# SENSOR.net
KiCad netlist of a schematic drawn in Altium Designer
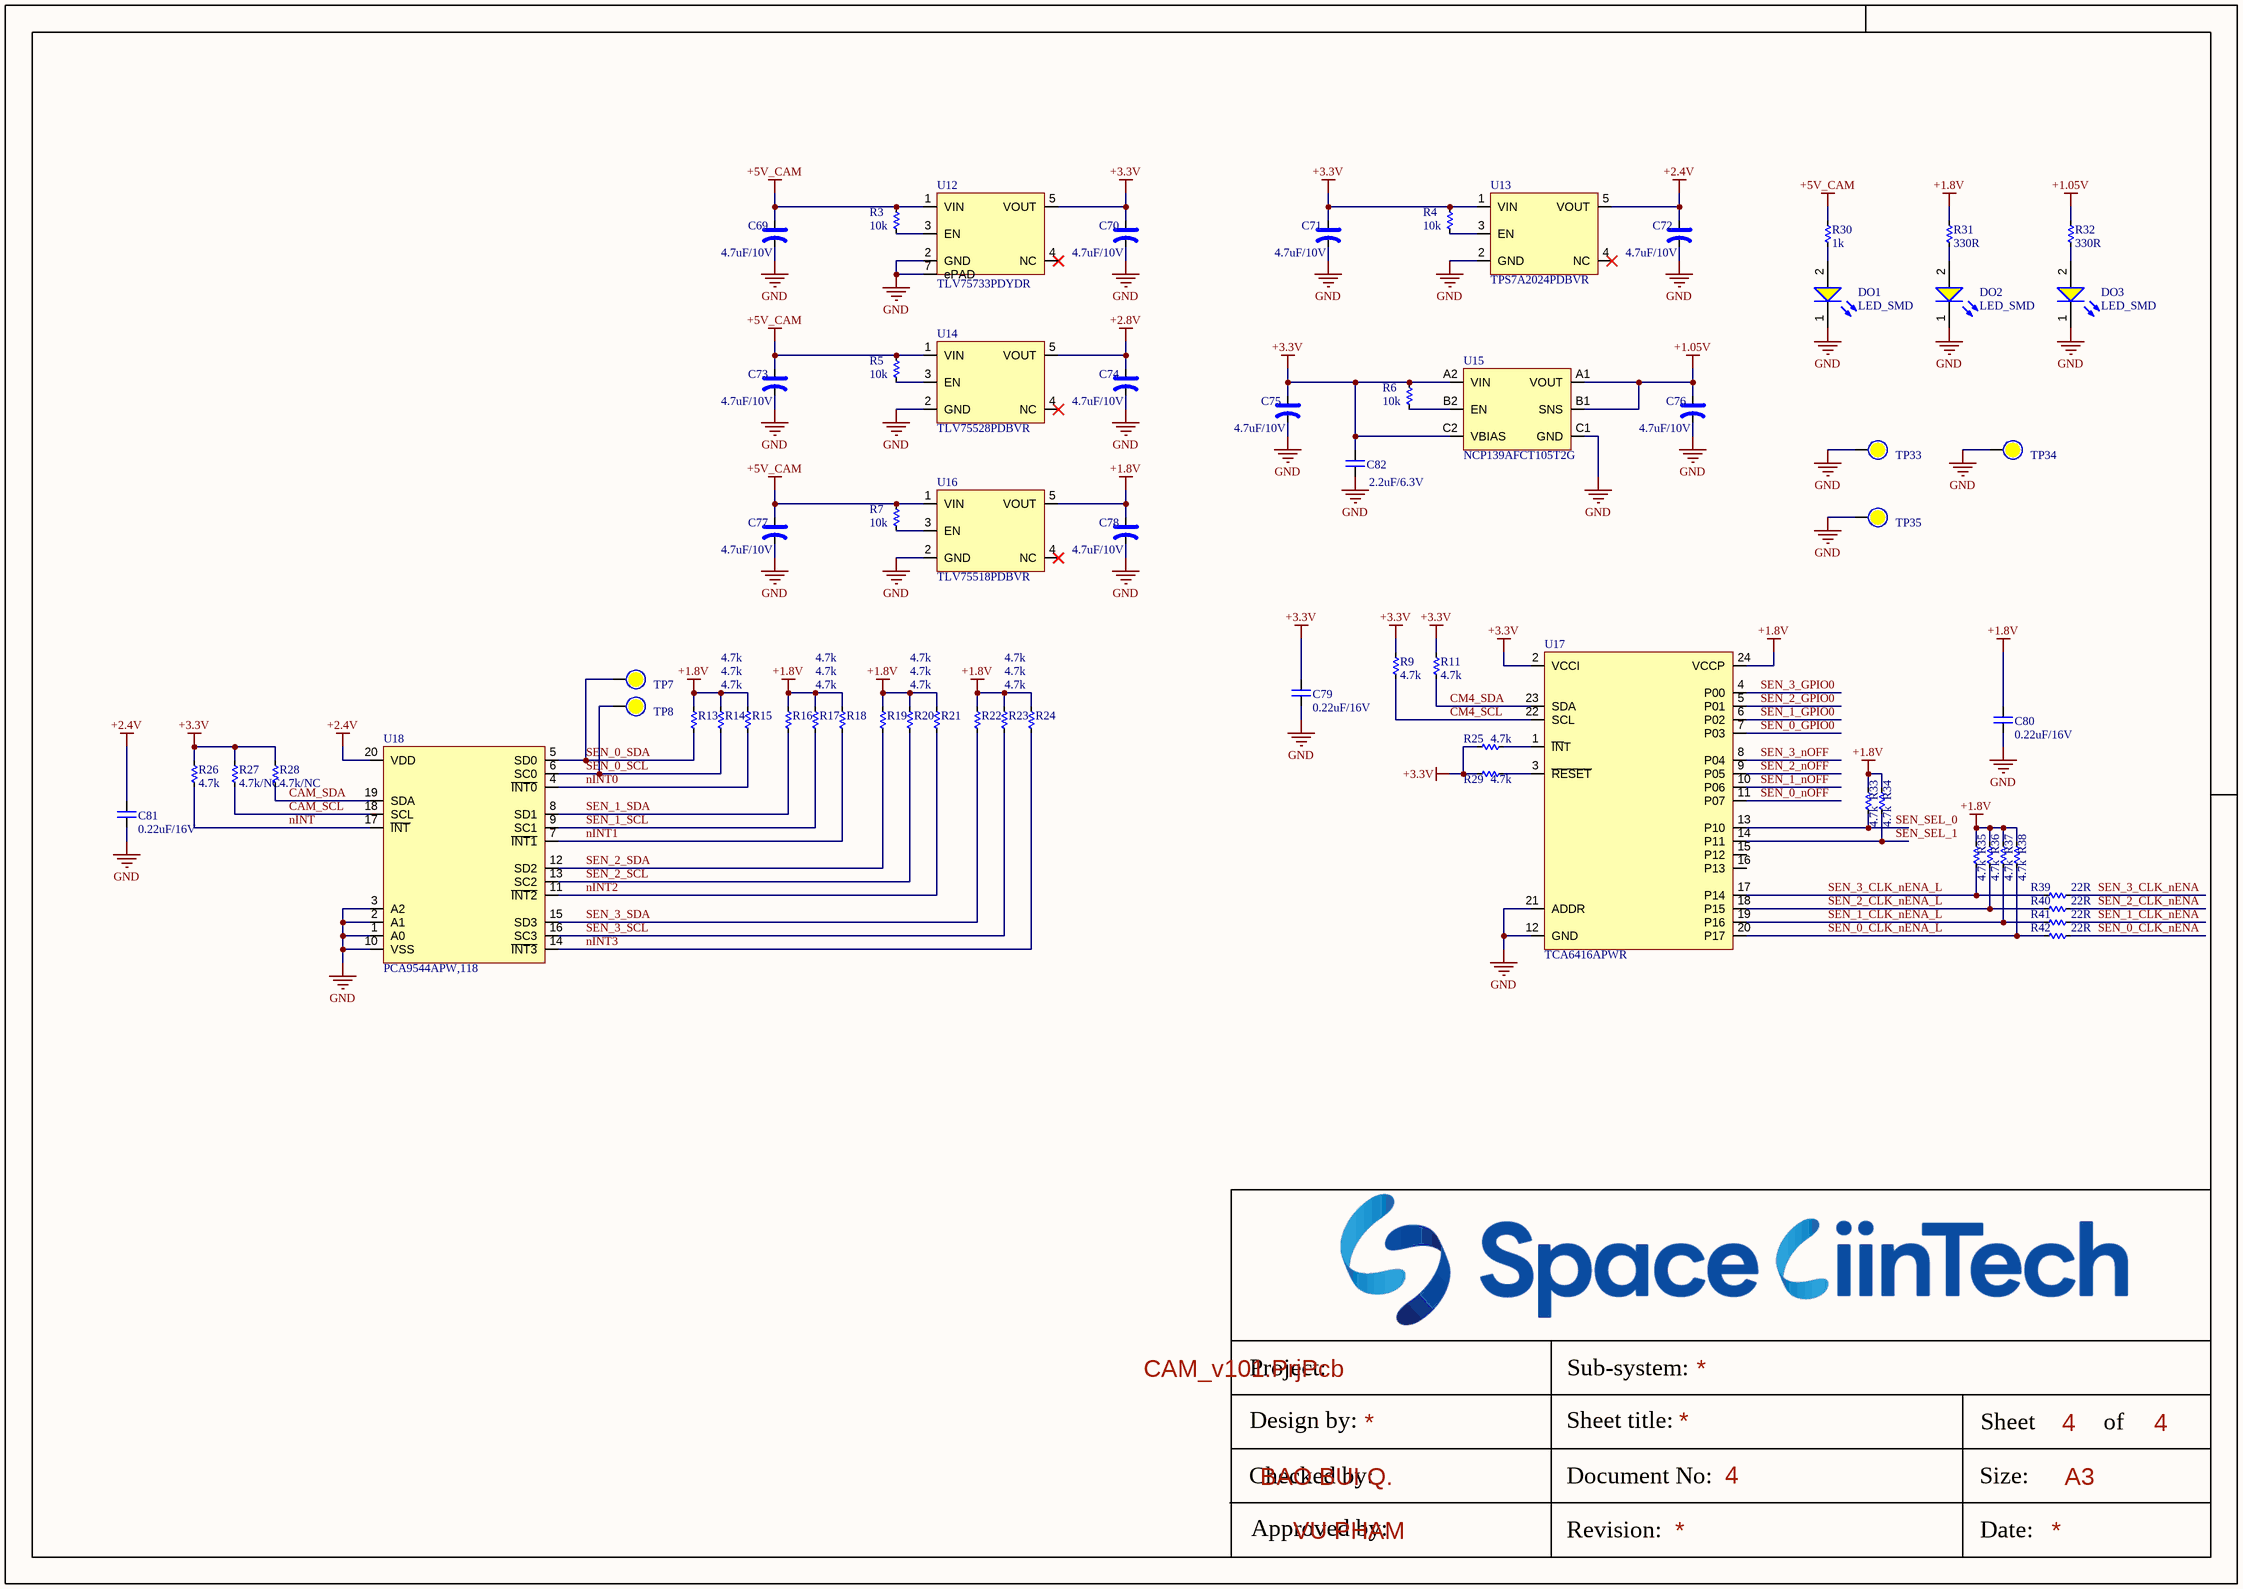
[diagram p0: SENSOR.SchDoc]

(export (version "E")
  (design (tool "Eeschema 10.0.6"))
  (components
    (comp (ref "C69")
      (value "4.7uF/10V")
      (footprint "CAP_MP_1608X90")
      (description "CAP_Polarization")
      (fields (field (name "PUBLISHER") "Altium Limited"))
      (libsource (lib "LABLIB") (part "CAP_TH"))
    )
    (comp (ref "C70")
      (value "4.7uF/10V")
      (footprint "CAP_MP_1608X90")
      (description "CAP_Polarization")
      (fields (field (name "PUBLISHER") "Altium Limited"))
      (libsource (lib "LABLIB") (part "CAP_TH"))
    )
    (comp (ref "C71")
      (value "4.7uF/10V")
      (footprint "CAP_MP_1608X90")
      (description "CAP_Polarization")
      (fields (field (name "PUBLISHER") "Altium Limited"))
      (libsource (lib "LABLIB") (part "CAP_TH"))
    )
    (comp (ref "C72")
      (value "4.7uF/10V")
      (footprint "CAP_MP_1608X90")
      (description "CAP_Polarization")
      (fields (field (name "PUBLISHER") "Altium Limited"))
      (libsource (lib "LABLIB") (part "CAP_TH"))
    )
    (comp (ref "C73")
      (value "4.7uF/10V")
      (footprint "CAP_MP_1608X90")
      (description "CAP_Polarization")
      (fields (field (name "PUBLISHER") "Altium Limited"))
      (libsource (lib "LABLIB") (part "CAP_TH"))
    )
    (comp (ref "C74")
      (value "4.7uF/10V")
      (footprint "CAP_MP_1608X90")
      (description "CAP_Polarization")
      (fields (field (name "PUBLISHER") "Altium Limited"))
      (libsource (lib "LABLIB") (part "CAP_TH"))
    )
    (comp (ref "C75")
      (value "4.7uF/10V")
      (footprint "CAP_MP_1608X90")
      (description "CAP_Polarization")
      (fields (field (name "PUBLISHER") "Altium Limited"))
      (libsource (lib "LABLIB") (part "CAP_TH"))
    )
    (comp (ref "C76")
      (value "4.7uF/10V")
      (footprint "CAP_MP_1608X90")
      (description "CAP_Polarization")
      (fields (field (name "PUBLISHER") "Altium Limited"))
      (libsource (lib "LABLIB") (part "CAP_TH"))
    )
    (comp (ref "C77")
      (value "4.7uF/10V")
      (footprint "CAP_MP_1608X90")
      (description "CAP_Polarization")
      (fields (field (name "PUBLISHER") "Altium Limited"))
      (libsource (lib "LABLIB") (part "CAP_TH"))
    )
    (comp (ref "C78")
      (value "4.7uF/10V")
      (footprint "CAP_MP_1608X90")
      (description "CAP_Polarization")
      (fields (field (name "PUBLISHER") "Altium Limited"))
      (libsource (lib "LABLIB") (part "CAP_TH"))
    )
    (comp (ref "C79")
      (value "0.22uF/16V")
      (footprint "CAP_C_1005X60")
      (description "CAP_Chip")
      (libsource (lib "LABLIB") (part "CAP_SMD"))
    )
    (comp (ref "C80")
      (value "0.22uF/16V")
      (footprint "CAP_C_1005X60")
      (description "CAP_Chip")
      (libsource (lib "LABLIB") (part "CAP_SMD"))
    )
    (comp (ref "C81")
      (value "0.22uF/16V")
      (footprint "CAP_C_1005X60")
      (description "CAP_Chip")
      (libsource (lib "LABLIB") (part "CAP_SMD"))
    )
    (comp (ref "C82")
      (value "2.2uF/6.3V")
      (footprint "CAP_C_1005X60")
      (description "CAP_Chip")
      (libsource (lib "LABLIB") (part "CAP_SMD"))
    )
    (comp (ref "DO1") (value "LED_SMD") (footprint "LED_0603") (libsource (lib "LABLIB") (part "LED_SMD")))
    (comp (ref "DO2") (value "LED_SMD") (footprint "LED_0603") (libsource (lib "LABLIB") (part "LED_SMD")))
    (comp (ref "DO3") (value "LED_SMD") (footprint "LED_0603") (libsource (lib "LABLIB") (part "LED_SMD")))
    (comp (ref "R3")
      (value "10k")
      (footprint "RES_C_1005X40")
      (description "RES-Chip")
      (fields
        (field (name "MANUFACTURER") "Generic Components")
        (field (name "PUBLISHER") "Altium Hobart Technology Centre")
      )
      (libsource (lib "LABLIB") (part "RES-SMD"))
    )
    (comp (ref "R4")
      (value "10k")
      (footprint "RES_C_1005X40")
      (description "RES-Chip")
      (fields
        (field (name "MANUFACTURER") "Generic Components")
        (field (name "PUBLISHER") "Altium Hobart Technology Centre")
      )
      (libsource (lib "LABLIB") (part "RES-SMD"))
    )
    (comp (ref "R5")
      (value "10k")
      (footprint "RES_C_1005X40")
      (description "RES-Chip")
      (fields
        (field (name "MANUFACTURER") "Generic Components")
        (field (name "PUBLISHER") "Altium Hobart Technology Centre")
      )
      (libsource (lib "LABLIB") (part "RES-SMD"))
    )
    (comp (ref "R6")
      (value "10k")
      (footprint "RES_C_1005X40")
      (description "RES-Chip")
      (fields
        (field (name "MANUFACTURER") "Generic Components")
        (field (name "PUBLISHER") "Altium Hobart Technology Centre")
      )
      (libsource (lib "LABLIB") (part "RES-SMD"))
    )
    (comp (ref "R7")
      (value "10k")
      (footprint "RES_C_1005X40")
      (description "RES-Chip")
      (fields
        (field (name "MANUFACTURER") "Generic Components")
        (field (name "PUBLISHER") "Altium Hobart Technology Centre")
      )
      (libsource (lib "LABLIB") (part "RES-SMD"))
    )
    (comp (ref "R9")
      (value "4.7k")
      (footprint "RES_C_1005X40")
      (description "RES-Chip")
      (fields
        (field (name "MANUFACTURER") "Generic Components")
        (field (name "PUBLISHER") "Altium Hobart Technology Centre")
      )
      (libsource (lib "LABLIB") (part "RES-SMD"))
    )
    (comp (ref "R11")
      (value "4.7k")
      (footprint "RES_C_1005X40")
      (description "RES-Chip")
      (fields
        (field (name "MANUFACTURER") "Generic Components")
        (field (name "PUBLISHER") "Altium Hobart Technology Centre")
      )
      (libsource (lib "LABLIB") (part "RES-SMD"))
    )
    (comp (ref "R13")
      (value "4.7k")
      (footprint "RES_C_1005X40")
      (description "RES-Chip")
      (fields
        (field (name "MANUFACTURER") "Generic Components")
        (field (name "PUBLISHER") "Altium Hobart Technology Centre")
      )
      (libsource (lib "LABLIB") (part "RES-SMD"))
    )
    (comp (ref "R14")
      (value "4.7k")
      (footprint "RES_C_1005X40")
      (description "RES-Chip")
      (fields
        (field (name "MANUFACTURER") "Generic Components")
        (field (name "PUBLISHER") "Altium Hobart Technology Centre")
      )
      (libsource (lib "LABLIB") (part "RES-SMD"))
    )
    (comp (ref "R15")
      (value "4.7k")
      (footprint "RES_C_1005X40")
      (description "RES-Chip")
      (fields
        (field (name "MANUFACTURER") "Generic Components")
        (field (name "PUBLISHER") "Altium Hobart Technology Centre")
      )
      (libsource (lib "LABLIB") (part "RES-SMD"))
    )
    (comp (ref "R16")
      (value "4.7k")
      (footprint "RES_C_1005X40")
      (description "RES-Chip")
      (fields
        (field (name "MANUFACTURER") "Generic Components")
        (field (name "PUBLISHER") "Altium Hobart Technology Centre")
      )
      (libsource (lib "LABLIB") (part "RES-SMD"))
    )
    (comp (ref "R17")
      (value "4.7k")
      (footprint "RES_C_1005X40")
      (description "RES-Chip")
      (fields
        (field (name "MANUFACTURER") "Generic Components")
        (field (name "PUBLISHER") "Altium Hobart Technology Centre")
      )
      (libsource (lib "LABLIB") (part "RES-SMD"))
    )
    (comp (ref "R18")
      (value "4.7k")
      (footprint "RES_C_1005X40")
      (description "RES-Chip")
      (fields
        (field (name "MANUFACTURER") "Generic Components")
        (field (name "PUBLISHER") "Altium Hobart Technology Centre")
      )
      (libsource (lib "LABLIB") (part "RES-SMD"))
    )
    (comp (ref "R19")
      (value "4.7k")
      (footprint "RES_C_1005X40")
      (description "RES-Chip")
      (fields
        (field (name "MANUFACTURER") "Generic Components")
        (field (name "PUBLISHER") "Altium Hobart Technology Centre")
      )
      (libsource (lib "LABLIB") (part "RES-SMD"))
    )
    (comp (ref "R20")
      (value "4.7k")
      (footprint "RES_C_1005X40")
      (description "RES-Chip")
      (fields
        (field (name "MANUFACTURER") "Generic Components")
        (field (name "PUBLISHER") "Altium Hobart Technology Centre")
      )
      (libsource (lib "LABLIB") (part "RES-SMD"))
    )
    (comp (ref "R21")
      (value "4.7k")
      (footprint "RES_C_1005X40")
      (description "RES-Chip")
      (fields
        (field (name "MANUFACTURER") "Generic Components")
        (field (name "PUBLISHER") "Altium Hobart Technology Centre")
      )
      (libsource (lib "LABLIB") (part "RES-SMD"))
    )
    (comp (ref "R22")
      (value "4.7k")
      (footprint "RES_C_1005X40")
      (description "RES-Chip")
      (fields
        (field (name "MANUFACTURER") "Generic Components")
        (field (name "PUBLISHER") "Altium Hobart Technology Centre")
      )
      (libsource (lib "LABLIB") (part "RES-SMD"))
    )
    (comp (ref "R23")
      (value "4.7k")
      (footprint "RES_C_1005X40")
      (description "RES-Chip")
      (fields
        (field (name "MANUFACTURER") "Generic Components")
        (field (name "PUBLISHER") "Altium Hobart Technology Centre")
      )
      (libsource (lib "LABLIB") (part "RES-SMD"))
    )
    (comp (ref "R24")
      (value "4.7k")
      (footprint "RES_C_1005X40")
      (description "RES-Chip")
      (fields
        (field (name "MANUFACTURER") "Generic Components")
        (field (name "PUBLISHER") "Altium Hobart Technology Centre")
      )
      (libsource (lib "LABLIB") (part "RES-SMD"))
    )
    (comp (ref "R25")
      (value "4.7k")
      (footprint "RES_C_1005X40")
      (description "RES-Chip")
      (fields
        (field (name "MANUFACTURER") "Generic Components")
        (field (name "PUBLISHER") "Altium Hobart Technology Centre")
      )
      (libsource (lib "LABLIB") (part "RES-SMD"))
    )
    (comp (ref "R26")
      (value "4.7k")
      (footprint "RES_C_1005X40")
      (description "RES-Chip")
      (fields
        (field (name "MANUFACTURER") "Generic Components")
        (field (name "PUBLISHER") "Altium Hobart Technology Centre")
      )
      (libsource (lib "LABLIB") (part "RES-SMD"))
    )
    (comp (ref "R27")
      (value "4.7k/NC")
      (footprint "RES_C_1005X40")
      (description "RES-Chip")
      (fields
        (field (name "MANUFACTURER") "Generic Components")
        (field (name "PUBLISHER") "Altium Hobart Technology Centre")
      )
      (libsource (lib "LABLIB") (part "RES-SMD"))
    )
    (comp (ref "R28")
      (value "4.7k/NC")
      (footprint "RES_C_1005X40")
      (description "RES-Chip")
      (fields
        (field (name "MANUFACTURER") "Generic Components")
        (field (name "PUBLISHER") "Altium Hobart Technology Centre")
      )
      (libsource (lib "LABLIB") (part "RES-SMD"))
    )
    (comp (ref "R29")
      (value "4.7k")
      (footprint "RES_C_1005X40")
      (description "RES-Chip")
      (fields
        (field (name "MANUFACTURER") "Generic Components")
        (field (name "PUBLISHER") "Altium Hobart Technology Centre")
      )
      (libsource (lib "LABLIB") (part "RES-SMD"))
    )
    (comp (ref "R30")
      (value "1k")
      (footprint "RES_C_1005X40")
      (description "RES-Chip")
      (fields
        (field (name "MANUFACTURER") "Generic Components")
        (field (name "PUBLISHER") "Altium Hobart Technology Centre")
      )
      (libsource (lib "LABLIB") (part "RES-SMD"))
    )
    (comp (ref "R31")
      (value "330R")
      (footprint "RES_C_1005X40")
      (description "RES-Chip")
      (fields
        (field (name "MANUFACTURER") "Generic Components")
        (field (name "PUBLISHER") "Altium Hobart Technology Centre")
      )
      (libsource (lib "LABLIB") (part "RES-SMD"))
    )
    (comp (ref "R32")
      (value "330R")
      (footprint "RES_C_1005X40")
      (description "RES-Chip")
      (fields
        (field (name "MANUFACTURER") "Generic Components")
        (field (name "PUBLISHER") "Altium Hobart Technology Centre")
      )
      (libsource (lib "LABLIB") (part "RES-SMD"))
    )
    (comp (ref "R33")
      (value "4.7k")
      (footprint "RES_C_1005X40")
      (description "RES-Chip")
      (fields
        (field (name "MANUFACTURER") "Generic Components")
        (field (name "PUBLISHER") "Altium Hobart Technology Centre")
      )
      (libsource (lib "LABLIB") (part "RES-SMD"))
    )
    (comp (ref "R34")
      (value "4.7k")
      (footprint "RES_C_1005X40")
      (description "RES-Chip")
      (fields
        (field (name "MANUFACTURER") "Generic Components")
        (field (name "PUBLISHER") "Altium Hobart Technology Centre")
      )
      (libsource (lib "LABLIB") (part "RES-SMD"))
    )
    (comp (ref "R35")
      (value "4.7k")
      (footprint "RES_C_1005X40")
      (description "RES-Chip")
      (fields
        (field (name "MANUFACTURER") "Generic Components")
        (field (name "PUBLISHER") "Altium Hobart Technology Centre")
      )
      (libsource (lib "LABLIB") (part "RES-SMD"))
    )
    (comp (ref "R36")
      (value "4.7k")
      (footprint "RES_C_1005X40")
      (description "RES-Chip")
      (fields
        (field (name "MANUFACTURER") "Generic Components")
        (field (name "PUBLISHER") "Altium Hobart Technology Centre")
      )
      (libsource (lib "LABLIB") (part "RES-SMD"))
    )
    (comp (ref "R37")
      (value "4.7k")
      (footprint "RES_C_1005X40")
      (description "RES-Chip")
      (fields
        (field (name "MANUFACTURER") "Generic Components")
        (field (name "PUBLISHER") "Altium Hobart Technology Centre")
      )
      (libsource (lib "LABLIB") (part "RES-SMD"))
    )
    (comp (ref "R38")
      (value "4.7k")
      (footprint "RES_C_1005X40")
      (description "RES-Chip")
      (fields
        (field (name "MANUFACTURER") "Generic Components")
        (field (name "PUBLISHER") "Altium Hobart Technology Centre")
      )
      (libsource (lib "LABLIB") (part "RES-SMD"))
    )
    (comp (ref "R39")
      (value "22R")
      (footprint "RES_C_1005X40")
      (description "RES-Chip")
      (fields
        (field (name "MANUFACTURER") "Generic Components")
        (field (name "PUBLISHER") "Altium Hobart Technology Centre")
      )
      (libsource (lib "LABLIB") (part "RES-SMD"))
    )
    (comp (ref "R40")
      (value "22R")
      (footprint "RES_C_1005X40")
      (description "RES-Chip")
      (fields
        (field (name "MANUFACTURER") "Generic Components")
        (field (name "PUBLISHER") "Altium Hobart Technology Centre")
      )
      (libsource (lib "LABLIB") (part "RES-SMD"))
    )
    (comp (ref "R41")
      (value "22R")
      (footprint "RES_C_1005X40")
      (description "RES-Chip")
      (fields
        (field (name "MANUFACTURER") "Generic Components")
        (field (name "PUBLISHER") "Altium Hobart Technology Centre")
      )
      (libsource (lib "LABLIB") (part "RES-SMD"))
    )
    (comp (ref "R42")
      (value "22R")
      (footprint "RES_C_1005X40")
      (description "RES-Chip")
      (fields
        (field (name "MANUFACTURER") "Generic Components")
        (field (name "PUBLISHER") "Altium Hobart Technology Centre")
      )
      (libsource (lib "LABLIB") (part "RES-SMD"))
    )
    (comp (ref "TP7")
      (value "~")
      (footprint "Testpoint_80")
      (description "Test Point")
      (libsource (lib "LABLIB") (part "Test Point"))
    )
    (comp (ref "TP8")
      (value "~")
      (footprint "Testpoint_80")
      (description "Test Point")
      (libsource (lib "LABLIB") (part "Test Point"))
    )
    (comp (ref "TP33")
      (value "~")
      (footprint "Testpoint_80")
      (description "Test Point")
      (libsource (lib "LABLIB") (part "Test Point"))
    )
    (comp (ref "TP34")
      (value "~")
      (footprint "Testpoint_80")
      (description "Test Point")
      (libsource (lib "LABLIB") (part "Test Point"))
    )
    (comp (ref "TP35")
      (value "~")
      (footprint "Testpoint_80")
      (description "Test Point")
      (libsource (lib "LABLIB") (part "Test Point"))
    )
    (comp (ref "U12")
      (value "TLV75733PDYDR")
      (footprint "SOT25-EPAD")
      (libsource (lib "CAMERA_SchLib") (part "IC_POWER_TLV75733PDYDR"))
    )
    (comp (ref "U13")
      (value "TPS7A2024PDBVR")
      (footprint "SOT25")
      (libsource (lib "CAMERA_SchLib") (part "IC_POWER_AP7347DQ"))
    )
    (comp (ref "U14")
      (value "TLV75528PDBVR")
      (footprint "SOT25")
      (libsource (lib "CAMERA_SchLib") (part "IC_POWER_AP7347DQ"))
    )
    (comp (ref "U15")
      (value "NCP139AFCT105T2G")
      (footprint "WLCSP6")
      (libsource (lib "CAMERA_SchLib") (part "IC_POWER_NCP139AFCT105T2G"))
    )
    (comp (ref "U16")
      (value "TLV75518PDBVR")
      (footprint "SOT25")
      (libsource (lib "CAMERA_SchLib") (part "IC_POWER_AP7347DQ"))
    )
    (comp (ref "U17")
      (value "TCA6416APWR")
      (footprint "SOP65P440W-24N")
      (libsource (lib "CAMERA_SchLib") (part "IC_I2Cto16IO_TCA6416APWR"))
    )
    (comp (ref "U18")
      (value "PCA9544APW,118")
      (footprint "SOP65P440W_20")
      (libsource (lib "CAMERA_SchLib") (part "IC_I2CSW1to4_PCA9544APW,118"))
    )
  )
  (nets
    (net (code "1") (name "+1.05V") (class "Default")
      (node (ref "C76") (pin "1") (pinfunction "1_1") (pintype "passive"))
      (node (ref "R32") (pin "1") (pinfunction "1_1") (pintype "passive"))
      (node (ref "U15") (pin "A1") (pinfunction "VOUT_A1") (pintype "passive"))
      (node (ref "U15") (pin "B1") (pinfunction "SNS_B1") (pintype "passive"))
    )
    (net (code "2") (name "+1.8V") (class "Default")
      (node (ref "C78") (pin "1") (pinfunction "1_1") (pintype "passive"))
      (node (ref "C80") (pin "2") (pinfunction "2_2") (pintype "passive"))
      (node (ref "R13") (pin "1") (pinfunction "1_1") (pintype "passive"))
      (node (ref "R14") (pin "1") (pinfunction "1_1") (pintype "passive"))
      (node (ref "R15") (pin "1") (pinfunction "1_1") (pintype "passive"))
      (node (ref "R16") (pin "1") (pinfunction "1_1") (pintype "passive"))
      (node (ref "R17") (pin "1") (pinfunction "1_1") (pintype "passive"))
      (node (ref "R18") (pin "1") (pinfunction "1_1") (pintype "passive"))
      (node (ref "R19") (pin "1") (pinfunction "1_1") (pintype "passive"))
      (node (ref "R20") (pin "1") (pinfunction "1_1") (pintype "passive"))
      (node (ref "R21") (pin "1") (pinfunction "1_1") (pintype "passive"))
      (node (ref "R22") (pin "1") (pinfunction "1_1") (pintype "passive"))
      (node (ref "R23") (pin "1") (pinfunction "1_1") (pintype "passive"))
      (node (ref "R24") (pin "1") (pinfunction "1_1") (pintype "passive"))
      (node (ref "R31") (pin "1") (pinfunction "1_1") (pintype "passive"))
      (node (ref "R33") (pin "1") (pinfunction "1_1") (pintype "passive"))
      (node (ref "R34") (pin "1") (pinfunction "1_1") (pintype "passive"))
      (node (ref "R35") (pin "1") (pinfunction "1_1") (pintype "passive"))
      (node (ref "R36") (pin "1") (pinfunction "1_1") (pintype "passive"))
      (node (ref "R37") (pin "1") (pinfunction "1_1") (pintype "passive"))
      (node (ref "R38") (pin "1") (pinfunction "1_1") (pintype "passive"))
      (node (ref "U16") (pin "5") (pinfunction "VOUT_5") (pintype "passive"))
      (node (ref "U17") (pin "24") (pinfunction "VCCP_24") (pintype "passive"))
    )
    (net (code "3") (name "+2.4V") (class "Default")
      (node (ref "C72") (pin "1") (pinfunction "1_1") (pintype "passive"))
      (node (ref "C81") (pin "2") (pinfunction "2_2") (pintype "passive"))
      (node (ref "U13") (pin "5") (pinfunction "VOUT_5") (pintype "passive"))
      (node (ref "U18") (pin "20") (pinfunction "VDD_20") (pintype "passive"))
    )
    (net (code "4") (name "+2.8V") (class "Default")
      (node (ref "C74") (pin "1") (pinfunction "1_1") (pintype "passive"))
      (node (ref "U14") (pin "5") (pinfunction "VOUT_5") (pintype "passive"))
    )
    (net (code "5") (name "+3.3V") (class "Default")
      (node (ref "C70") (pin "1") (pinfunction "1_1") (pintype "passive"))
      (node (ref "C71") (pin "1") (pinfunction "1_1") (pintype "passive"))
      (node (ref "C75") (pin "1") (pinfunction "1_1") (pintype "passive"))
      (node (ref "C79") (pin "2") (pinfunction "2_2") (pintype "passive"))
      (node (ref "C82") (pin "2") (pinfunction "2_2") (pintype "passive"))
      (node (ref "R11") (pin "1") (pinfunction "1_1") (pintype "passive"))
      (node (ref "R25") (pin "1") (pinfunction "1_1") (pintype "passive"))
      (node (ref "R26") (pin "1") (pinfunction "1_1") (pintype "passive"))
      (node (ref "R27") (pin "1") (pinfunction "1_1") (pintype "passive"))
      (node (ref "R28") (pin "1") (pinfunction "1_1") (pintype "passive"))
      (node (ref "R29") (pin "1") (pinfunction "1_1") (pintype "passive"))
      (node (ref "R4") (pin "2") (pinfunction "2_2") (pintype "passive"))
      (node (ref "R6") (pin "2") (pinfunction "2_2") (pintype "passive"))
      (node (ref "R9") (pin "1") (pinfunction "1_1") (pintype "passive"))
      (node (ref "U12") (pin "5") (pinfunction "VOUT_5") (pintype "passive"))
      (node (ref "U13") (pin "1") (pinfunction "VIN_1") (pintype "passive"))
      (node (ref "U15") (pin "A2") (pinfunction "VIN_A2") (pintype "passive"))
      (node (ref "U15") (pin "C2") (pinfunction "VBIAS_C2") (pintype "passive"))
      (node (ref "U17") (pin "2") (pinfunction "VCCI_2") (pintype "passive"))
    )
    (net (code "6") (name "+5V_CAM") (class "Default")
      (node (ref "C69") (pin "1") (pinfunction "1_1") (pintype "passive"))
      (node (ref "C73") (pin "1") (pinfunction "1_1") (pintype "passive"))
      (node (ref "C77") (pin "1") (pinfunction "1_1") (pintype "passive"))
      (node (ref "R3") (pin "2") (pinfunction "2_2") (pintype "passive"))
      (node (ref "R30") (pin "1") (pinfunction "1_1") (pintype "passive"))
      (node (ref "R5") (pin "2") (pinfunction "2_2") (pintype "passive"))
      (node (ref "R7") (pin "2") (pinfunction "2_2") (pintype "passive"))
      (node (ref "U12") (pin "1") (pinfunction "VIN_1") (pintype "passive"))
      (node (ref "U14") (pin "1") (pinfunction "VIN_1") (pintype "passive"))
      (node (ref "U16") (pin "1") (pinfunction "VIN_1") (pintype "passive"))
    )
    (net (code "7") (name "/CAM_SCL") (class "Default")
      (node (ref "R27") (pin "2") (pinfunction "2_2") (pintype "passive"))
      (node (ref "U18") (pin "18") (pinfunction "SCL_18") (pintype "passive"))
    )
    (net (code "8") (name "/CAM_SDA") (class "Default")
      (node (ref "R28") (pin "2") (pinfunction "2_2") (pintype "passive"))
      (node (ref "U18") (pin "19") (pinfunction "SDA_19") (pintype "passive"))
    )
    (net (code "9") (name "/CM4_SCL") (class "Default")
      (node (ref "R9") (pin "2") (pinfunction "2_2") (pintype "passive"))
      (node (ref "U17") (pin "22") (pinfunction "SCL_22") (pintype "passive"))
    )
    (net (code "10") (name "/CM4_SDA") (class "Default")
      (node (ref "R11") (pin "2") (pinfunction "2_2") (pintype "passive"))
      (node (ref "U17") (pin "23") (pinfunction "SDA_23") (pintype "passive"))
    )
    (net (code "11") (name "/SEN_0_CLK_nENA") (class "Default")
      (node (ref "R42") (pin "1") (pinfunction "1_1") (pintype "passive"))
    )
    (net (code "12") (name "/SEN_0_CLK_nENA_L") (class "Default")
      (node (ref "R38") (pin "2") (pinfunction "2_2") (pintype "passive"))
      (node (ref "R42") (pin "2") (pinfunction "2_2") (pintype "passive"))
      (node (ref "U17") (pin "20") (pinfunction "P17_20") (pintype "passive"))
    )
    (net (code "13") (name "/SEN_0_GPIO0") (class "Default")
      (node (ref "U17") (pin "7") (pinfunction "P03_7") (pintype "passive"))
    )
    (net (code "14") (name "/SEN_0_SCL") (class "Default")
      (node (ref "R14") (pin "2") (pinfunction "2_2") (pintype "passive"))
      (node (ref "TP8") (pin "0") (pinfunction "0_0") (pintype "passive"))
      (node (ref "U18") (pin "6") (pinfunction "SC0_6") (pintype "passive"))
    )
    (net (code "15") (name "/SEN_0_SDA") (class "Default")
      (node (ref "R13") (pin "2") (pinfunction "2_2") (pintype "passive"))
      (node (ref "TP7") (pin "0") (pinfunction "0_0") (pintype "passive"))
      (node (ref "U18") (pin "5") (pinfunction "SD0_5") (pintype "passive"))
    )
    (net (code "16") (name "/SEN_0_nOFF") (class "Default")
      (node (ref "U17") (pin "11") (pinfunction "P07_11") (pintype "passive"))
    )
    (net (code "17") (name "/SEN_1_CLK_nENA") (class "Default")
      (node (ref "R41") (pin "1") (pinfunction "1_1") (pintype "passive"))
    )
    (net (code "18") (name "/SEN_1_CLK_nENA_L") (class "Default")
      (node (ref "R37") (pin "2") (pinfunction "2_2") (pintype "passive"))
      (node (ref "R41") (pin "2") (pinfunction "2_2") (pintype "passive"))
      (node (ref "U17") (pin "19") (pinfunction "P16_19") (pintype "passive"))
    )
    (net (code "19") (name "/SEN_1_GPIO0") (class "Default")
      (node (ref "U17") (pin "6") (pinfunction "P02_6") (pintype "passive"))
    )
    (net (code "20") (name "/SEN_1_SCL") (class "Default")
      (node (ref "R17") (pin "2") (pinfunction "2_2") (pintype "passive"))
      (node (ref "U18") (pin "9") (pinfunction "SC1_9") (pintype "passive"))
    )
    (net (code "21") (name "/SEN_1_SDA") (class "Default")
      (node (ref "R16") (pin "2") (pinfunction "2_2") (pintype "passive"))
      (node (ref "U18") (pin "8") (pinfunction "SD1_8") (pintype "passive"))
    )
    (net (code "22") (name "/SEN_1_nOFF") (class "Default")
      (node (ref "U17") (pin "10") (pinfunction "P06_10") (pintype "passive"))
    )
    (net (code "23") (name "/SEN_2_CLK_nENA") (class "Default")
      (node (ref "R40") (pin "1") (pinfunction "1_1") (pintype "passive"))
    )
    (net (code "24") (name "/SEN_2_CLK_nENA_L") (class "Default")
      (node (ref "R36") (pin "2") (pinfunction "2_2") (pintype "passive"))
      (node (ref "R40") (pin "2") (pinfunction "2_2") (pintype "passive"))
      (node (ref "U17") (pin "18") (pinfunction "P15_18") (pintype "passive"))
    )
    (net (code "25") (name "/SEN_2_GPIO0") (class "Default")
      (node (ref "U17") (pin "5") (pinfunction "P01_5") (pintype "passive"))
    )
    (net (code "26") (name "/SEN_2_SCL") (class "Default")
      (node (ref "R20") (pin "2") (pinfunction "2_2") (pintype "passive"))
      (node (ref "U18") (pin "13") (pinfunction "SC2_13") (pintype "passive"))
    )
    (net (code "27") (name "/SEN_2_SDA") (class "Default")
      (node (ref "R19") (pin "2") (pinfunction "2_2") (pintype "passive"))
      (node (ref "U18") (pin "12") (pinfunction "SD2_12") (pintype "passive"))
    )
    (net (code "28") (name "/SEN_2_nOFF") (class "Default")
      (node (ref "U17") (pin "9") (pinfunction "P05_9") (pintype "passive"))
    )
    (net (code "29") (name "/SEN_3_CLK_nENA") (class "Default")
      (node (ref "R39") (pin "1") (pinfunction "1_1") (pintype "passive"))
    )
    (net (code "30") (name "/SEN_3_CLK_nENA_L") (class "Default")
      (node (ref "R35") (pin "2") (pinfunction "2_2") (pintype "passive"))
      (node (ref "R39") (pin "2") (pinfunction "2_2") (pintype "passive"))
      (node (ref "U17") (pin "17") (pinfunction "P14_17") (pintype "passive"))
    )
    (net (code "31") (name "/SEN_3_GPIO0") (class "Default")
      (node (ref "U17") (pin "4") (pinfunction "P00_4") (pintype "passive"))
    )
    (net (code "32") (name "/SEN_3_SCL") (class "Default")
      (node (ref "R23") (pin "2") (pinfunction "2_2") (pintype "passive"))
      (node (ref "U18") (pin "16") (pinfunction "SC3_16") (pintype "passive"))
    )
    (net (code "33") (name "/SEN_3_SDA") (class "Default")
      (node (ref "R22") (pin "2") (pinfunction "2_2") (pintype "passive"))
      (node (ref "U18") (pin "15") (pinfunction "SD3_15") (pintype "passive"))
    )
    (net (code "34") (name "/SEN_3_nOFF") (class "Default")
      (node (ref "U17") (pin "8") (pinfunction "P04_8") (pintype "passive"))
    )
    (net (code "35") (name "/SEN_SEL_0") (class "Default")
      (node (ref "R33") (pin "2") (pinfunction "2_2") (pintype "passive"))
      (node (ref "U17") (pin "13") (pinfunction "P10_13") (pintype "passive"))
    )
    (net (code "36") (name "/SEN_SEL_1") (class "Default")
      (node (ref "R34") (pin "2") (pinfunction "2_2") (pintype "passive"))
      (node (ref "U17") (pin "14") (pinfunction "P11_14") (pintype "passive"))
    )
    (net (code "37") (name "/nINT") (class "Default")
      (node (ref "R26") (pin "2") (pinfunction "2_2") (pintype "passive"))
      (node (ref "U18") (pin "17") (pinfunction "~{INT}_17") (pintype "passive"))
    )
    (net (code "38") (name "/nINT0") (class "Default")
      (node (ref "R15") (pin "2") (pinfunction "2_2") (pintype "passive"))
      (node (ref "U18") (pin "4") (pinfunction "~{INT0}_4") (pintype "passive"))
    )
    (net (code "39") (name "/nINT1") (class "Default")
      (node (ref "R18") (pin "2") (pinfunction "2_2") (pintype "passive"))
      (node (ref "U18") (pin "7") (pinfunction "~{INT1}_7") (pintype "passive"))
    )
    (net (code "40") (name "/nINT2") (class "Default")
      (node (ref "R21") (pin "2") (pinfunction "2_2") (pintype "passive"))
      (node (ref "U18") (pin "11") (pinfunction "~{INT2}_11") (pintype "passive"))
    )
    (net (code "41") (name "/nINT3") (class "Default")
      (node (ref "R24") (pin "2") (pinfunction "2_2") (pintype "passive"))
      (node (ref "U18") (pin "14") (pinfunction "~{INT3}_14") (pintype "passive"))
    )
    (net (code "42") (name "GND") (class "Default")
      (node (ref "C69") (pin "2") (pinfunction "2_2") (pintype "passive"))
      (node (ref "C70") (pin "2") (pinfunction "2_2") (pintype "passive"))
      (node (ref "C71") (pin "2") (pinfunction "2_2") (pintype "passive"))
      (node (ref "C72") (pin "2") (pinfunction "2_2") (pintype "passive"))
      (node (ref "C73") (pin "2") (pinfunction "2_2") (pintype "passive"))
      (node (ref "C74") (pin "2") (pinfunction "2_2") (pintype "passive"))
      (node (ref "C75") (pin "2") (pinfunction "2_2") (pintype "passive"))
      (node (ref "C76") (pin "2") (pinfunction "2_2") (pintype "passive"))
      (node (ref "C77") (pin "2") (pinfunction "2_2") (pintype "passive"))
      (node (ref "C78") (pin "2") (pinfunction "2_2") (pintype "passive"))
      (node (ref "C79") (pin "1") (pinfunction "1_1") (pintype "passive"))
      (node (ref "C80") (pin "1") (pinfunction "1_1") (pintype "passive"))
      (node (ref "C81") (pin "1") (pinfunction "1_1") (pintype "passive"))
      (node (ref "C82") (pin "1") (pinfunction "1_1") (pintype "passive"))
      (node (ref "DO1") (pin "1") (pinfunction "K_1") (pintype "passive"))
      (node (ref "DO2") (pin "1") (pinfunction "K_1") (pintype "passive"))
      (node (ref "DO3") (pin "1") (pinfunction "K_1") (pintype "passive"))
      (node (ref "TP33") (pin "0") (pinfunction "0_0") (pintype "passive"))
      (node (ref "TP34") (pin "0") (pinfunction "0_0") (pintype "passive"))
      (node (ref "TP35") (pin "0") (pinfunction "0_0") (pintype "passive"))
      (node (ref "U12") (pin "2") (pinfunction "GND_2") (pintype "passive"))
      (node (ref "U12") (pin "7") (pinfunction "ePAD_7") (pintype "passive"))
      (node (ref "U13") (pin "2") (pinfunction "GND_2") (pintype "passive"))
      (node (ref "U14") (pin "2") (pinfunction "GND_2") (pintype "passive"))
      (node (ref "U15") (pin "C1") (pinfunction "GND_C1") (pintype "passive"))
      (node (ref "U16") (pin "2") (pinfunction "GND_2") (pintype "passive"))
      (node (ref "U17") (pin "12") (pinfunction "GND_12") (pintype "passive"))
      (node (ref "U17") (pin "21") (pinfunction "ADDR_21") (pintype "passive"))
      (node (ref "U18") (pin "1") (pinfunction "A0_1") (pintype "passive"))
      (node (ref "U18") (pin "10") (pinfunction "VSS_10") (pintype "passive"))
      (node (ref "U18") (pin "2") (pinfunction "A1_2") (pintype "passive"))
      (node (ref "U18") (pin "3") (pinfunction "A2_3") (pintype "passive"))
    )
    (net (code "43") (name "Net-(DO1-A)") (class "Default")
      (node (ref "DO1") (pin "2") (pinfunction "A_2") (pintype "passive"))
      (node (ref "R30") (pin "2") (pinfunction "2_2") (pintype "passive"))
    )
    (net (code "44") (name "Net-(DO2-A)") (class "Default")
      (node (ref "DO2") (pin "2") (pinfunction "A_2") (pintype "passive"))
      (node (ref "R31") (pin "2") (pinfunction "2_2") (pintype "passive"))
    )
    (net (code "45") (name "Net-(DO3-A)") (class "Default")
      (node (ref "DO3") (pin "2") (pinfunction "A_2") (pintype "passive"))
      (node (ref "R32") (pin "2") (pinfunction "2_2") (pintype "passive"))
    )
    (net (code "46") (name "Net-(U12-EN)") (class "Default")
      (node (ref "R3") (pin "1") (pinfunction "1_1") (pintype "passive"))
      (node (ref "U12") (pin "3") (pinfunction "EN_3") (pintype "passive"))
    )
    (net (code "47") (name "Net-(U13-EN)") (class "Default")
      (node (ref "R4") (pin "1") (pinfunction "1_1") (pintype "passive"))
      (node (ref "U13") (pin "3") (pinfunction "EN_3") (pintype "passive"))
    )
    (net (code "48") (name "Net-(U14-EN)") (class "Default")
      (node (ref "R5") (pin "1") (pinfunction "1_1") (pintype "passive"))
      (node (ref "U14") (pin "3") (pinfunction "EN_3") (pintype "passive"))
    )
    (net (code "49") (name "Net-(U15-EN)") (class "Default")
      (node (ref "R6") (pin "1") (pinfunction "1_1") (pintype "passive"))
      (node (ref "U15") (pin "B2") (pinfunction "EN_B2") (pintype "passive"))
    )
    (net (code "50") (name "Net-(U16-EN)") (class "Default")
      (node (ref "R7") (pin "1") (pinfunction "1_1") (pintype "passive"))
      (node (ref "U16") (pin "3") (pinfunction "EN_3") (pintype "passive"))
    )
    (net (code "51") (name "Net-(U17-~{IN}T)") (class "Default")
      (node (ref "R25") (pin "2") (pinfunction "2_2") (pintype "passive"))
      (node (ref "U17") (pin "1") (pinfunction "~{IN}T_1") (pintype "passive"))
    )
    (net (code "52") (name "Net-(U17-~{RESET})") (class "Default")
      (node (ref "R29") (pin "2") (pinfunction "2_2") (pintype "passive"))
      (node (ref "U17") (pin "3") (pinfunction "~{RESET}_3") (pintype "passive"))
    )
    (net (code "53") (name "unconnected-(U12-NC-Pad4)") (class "Default")
      (node (ref "U12") (pin "4") (pinfunction "NC_4") (pintype "passive+no_connect"))
    )
    (net (code "54") (name "unconnected-(U13-NC-Pad4)") (class "Default")
      (node (ref "U13") (pin "4") (pinfunction "NC_4") (pintype "passive+no_connect"))
    )
    (net (code "55") (name "unconnected-(U14-NC-Pad4)") (class "Default")
      (node (ref "U14") (pin "4") (pinfunction "NC_4") (pintype "passive+no_connect"))
    )
    (net (code "56") (name "unconnected-(U16-NC-Pad4)") (class "Default")
      (node (ref "U16") (pin "4") (pinfunction "NC_4") (pintype "passive+no_connect"))
    )
    (net (code "57") (name "unconnected-(U17-P12-Pad15)") (class "Default")
      (node (ref "U17") (pin "15") (pinfunction "P12_15") (pintype "passive"))
    )
    (net (code "58") (name "unconnected-(U17-P13-Pad16)") (class "Default")
      (node (ref "U17") (pin "16") (pinfunction "P13_16") (pintype "passive"))
    )
  )
)
